# simon.net
KiCad netlist of a schematic drawn in EAGLE
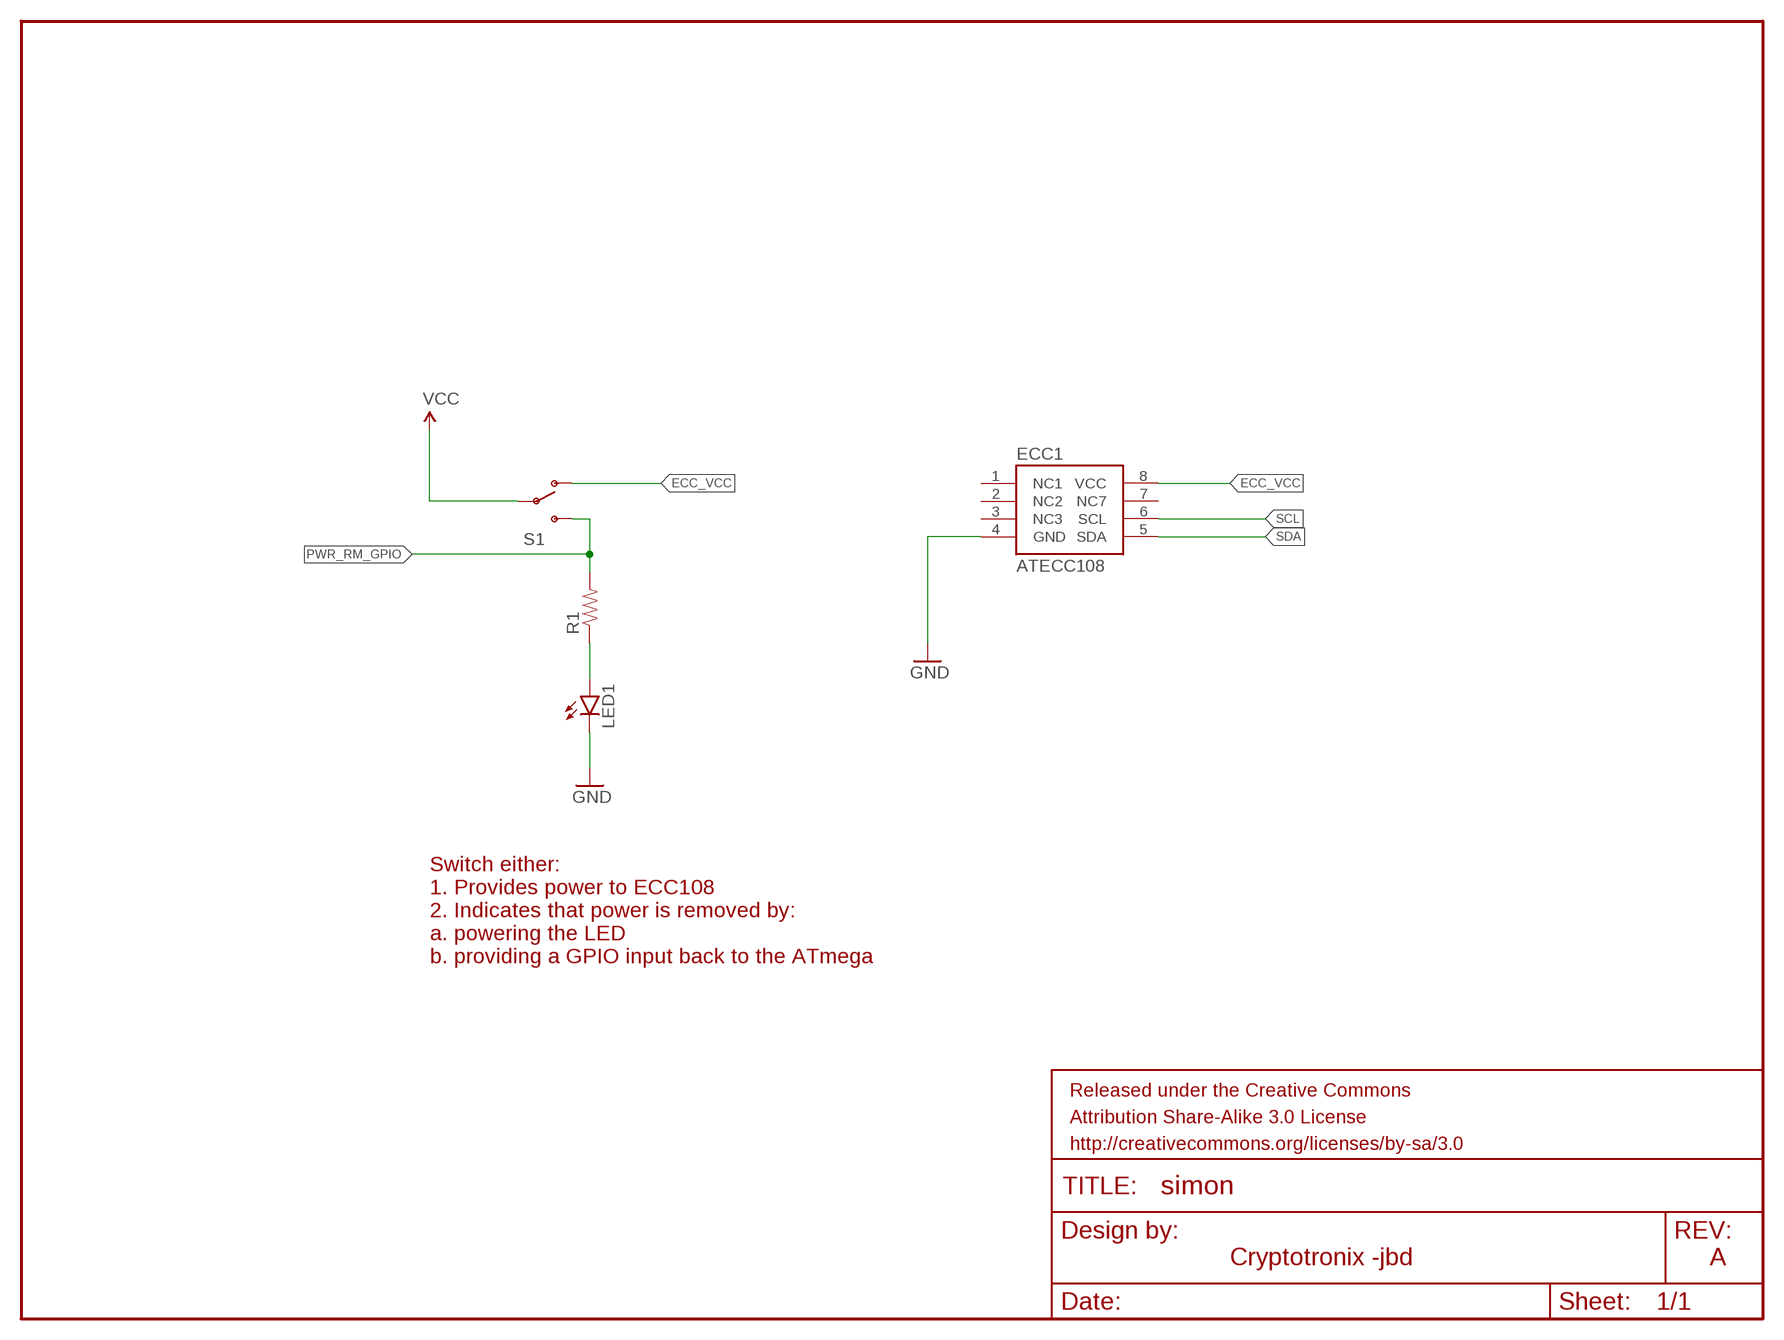
[diagram p0: schematic, sheet 1]

(export (version "E")
  (design (tool "Eeschema 10.0.6"))
  (components
    (comp (ref "ECC1")
      (value "ATECC108")
      (footprint "eagle-import:SOIC8")
      (libsource (lib "eagle-import") (part "ATECC108"))
    )
    (comp (ref "FRAME1")
      (value "FRAME-LETTER")
      (footprint "eagle-import:CREATIVE_COMMONS")
      (libsource (lib "eagle-import") (part "FRAME-LETTER"))
    )
    (comp (ref "LED1")
      (value "LED0603")
      (footprint "eagle-import:LED-0603")
      (libsource (lib "eagle-import") (part "LED0603"))
    )
    (comp (ref "R1")
      (value "RESISTOR0603")
      (footprint "eagle-import:0603-RES")
      (libsource (lib "eagle-import") (part "RESISTOR0603"))
    )
    (comp (ref "S1")
      (value "SWITCH-SPDT-SMD-A")
      (footprint "eagle-import:SWITCH-SPST-SMD-A")
      (libsource (lib "eagle-import") (part "SWITCH-SPDT-SMD-A"))
    )
  )
  (nets
    (net (code "1") (name "ECC_VCC") (class "Default")
      (node (ref "ECC1") (pin "8") (pinfunction "VCC_8") (pintype "power_in"))
      (node (ref "S1") (pin "1") (pinfunction "O_1") (pintype "passive"))
    )
    (net (code "2") (name "GND") (class "Default")
      (node (ref "ECC1") (pin "4") (pinfunction "GND_4") (pintype "power_in"))
      (node (ref "LED1") (pin "C") (pinfunction "C_C") (pintype "passive"))
    )
    (net (code "3") (name "Net-(LED1-PadA)") (class "Default")
      (node (ref "LED1") (pin "A") (pinfunction "A_A") (pintype "passive"))
      (node (ref "R1") (pin "1") (pinfunction "1_1") (pintype "passive"))
    )
    (net (code "4") (name "PWR_RM_GPIO") (class "Default")
      (node (ref "R1") (pin "2") (pinfunction "2_2") (pintype "passive"))
      (node (ref "S1") (pin "3") (pinfunction "S_3") (pintype "passive"))
    )
    (net (code "5") (name "SCL") (class "Default")
      (node (ref "ECC1") (pin "6") (pinfunction "SCL_6") (pintype "bidirectional"))
    )
    (net (code "6") (name "SDA") (class "Default")
      (node (ref "ECC1") (pin "5") (pinfunction "SDA_5") (pintype "bidirectional"))
    )
    (net (code "7") (name "VCC") (class "Default")
      (node (ref "S1") (pin "2") (pinfunction "P_2") (pintype "passive"))
    )
    (net (code "8") (name "unconnected-(ECC1-NC1-Pad1)") (class "Default")
      (node (ref "ECC1") (pin "1") (pinfunction "NC1_1") (pintype "bidirectional"))
    )
    (net (code "9") (name "unconnected-(ECC1-NC2-Pad2)") (class "Default")
      (node (ref "ECC1") (pin "2") (pinfunction "NC2_2") (pintype "no_connect"))
    )
    (net (code "10") (name "unconnected-(ECC1-NC3-Pad3)") (class "Default")
      (node (ref "ECC1") (pin "3") (pinfunction "NC3_3") (pintype "no_connect"))
    )
    (net (code "11") (name "unconnected-(ECC1-NC7-Pad7)") (class "Default")
      (node (ref "ECC1") (pin "7") (pinfunction "NC7_7") (pintype "no_connect"))
    )
  )
)
